# Afficheur_7_segments.net
KiCad netlist of a schematic drawn in Altium Designer
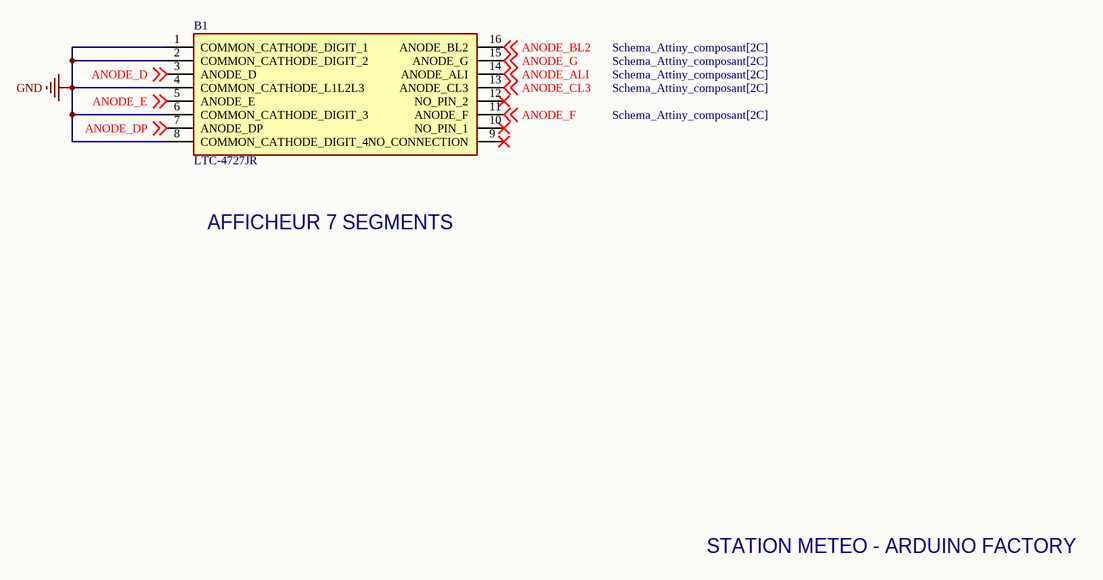
[diagram p0: Afficheur_7_segments.SchDoc]

(export (version "E")
  (design (tool "Eeschema 10.0.6"))
  (components
    (comp (ref "B1")
      (value "LTC-4727JR")
      (footprint "DIP1016W75P254L4018H725Q16N")
      (description "Displays Panel 4DIGIT 35LED Sup. Red CC 14-Pin DIP Module")
      (fields (field (name "MOUSER PART NUMBER") "859-LTC-4727JR"))
      (libsource (lib "LTC-4727JR") (part "LTC-4727JR"))
    )
  )
  (nets
    (net (code "1") (name "ANODE_ALI") (class "Default")
      (node (ref "B1") (pin "14") (pinfunction "ANODE_ALI_14") (pintype "passive"))
    )
    (net (code "2") (name "ANODE_BL2") (class "Default")
      (node (ref "B1") (pin "16") (pinfunction "ANODE_BL2_16") (pintype "passive"))
    )
    (net (code "3") (name "ANODE_CL3") (class "Default")
      (node (ref "B1") (pin "13") (pinfunction "ANODE_CL3_13") (pintype "passive"))
    )
    (net (code "4") (name "ANODE_D") (class "Default")
      (node (ref "B1") (pin "3") (pinfunction "ANODE_D_3") (pintype "passive"))
    )
    (net (code "5") (name "ANODE_DP") (class "Default")
      (node (ref "B1") (pin "7") (pinfunction "ANODE_DP_7") (pintype "passive"))
    )
    (net (code "6") (name "ANODE_E") (class "Default")
      (node (ref "B1") (pin "5") (pinfunction "ANODE_E_5") (pintype "passive"))
    )
    (net (code "7") (name "ANODE_F") (class "Default")
      (node (ref "B1") (pin "11") (pinfunction "ANODE_F_11") (pintype "passive"))
    )
    (net (code "8") (name "ANODE_G") (class "Default")
      (node (ref "B1") (pin "15") (pinfunction "ANODE_G_15") (pintype "passive"))
    )
    (net (code "9") (name "GND") (class "Default")
      (node (ref "B1") (pin "1") (pinfunction "COMMON_CATHODE_DIGIT_1_1") (pintype "passive"))
      (node (ref "B1") (pin "2") (pinfunction "COMMON_CATHODE_DIGIT_2_2") (pintype "passive"))
      (node (ref "B1") (pin "4") (pinfunction "COMMON_CATHODE_L1L2L3_4") (pintype "passive"))
      (node (ref "B1") (pin "6") (pinfunction "COMMON_CATHODE_DIGIT_3_6") (pintype "passive"))
      (node (ref "B1") (pin "8") (pinfunction "COMMON_CATHODE_DIGIT_4_8") (pintype "passive"))
    )
    (net (code "10") (name "unconnected-(B1-NO_CONNECTION-Pad9)") (class "Default")
      (node (ref "B1") (pin "9") (pinfunction "NO_CONNECTION_9") (pintype "passive+no_connect"))
    )
    (net (code "11") (name "unconnected-(B1-NO_PIN_1-Pad10)") (class "Default")
      (node (ref "B1") (pin "10") (pinfunction "NO_PIN_1_10") (pintype "passive+no_connect"))
    )
    (net (code "12") (name "unconnected-(B1-NO_PIN_2-Pad12)") (class "Default")
      (node (ref "B1") (pin "12") (pinfunction "NO_PIN_2_12") (pintype "passive+no_connect"))
    )
  )
)
